# Schaltplan_Ampel.net
KiCad netlist of a schematic drawn in EAGLE
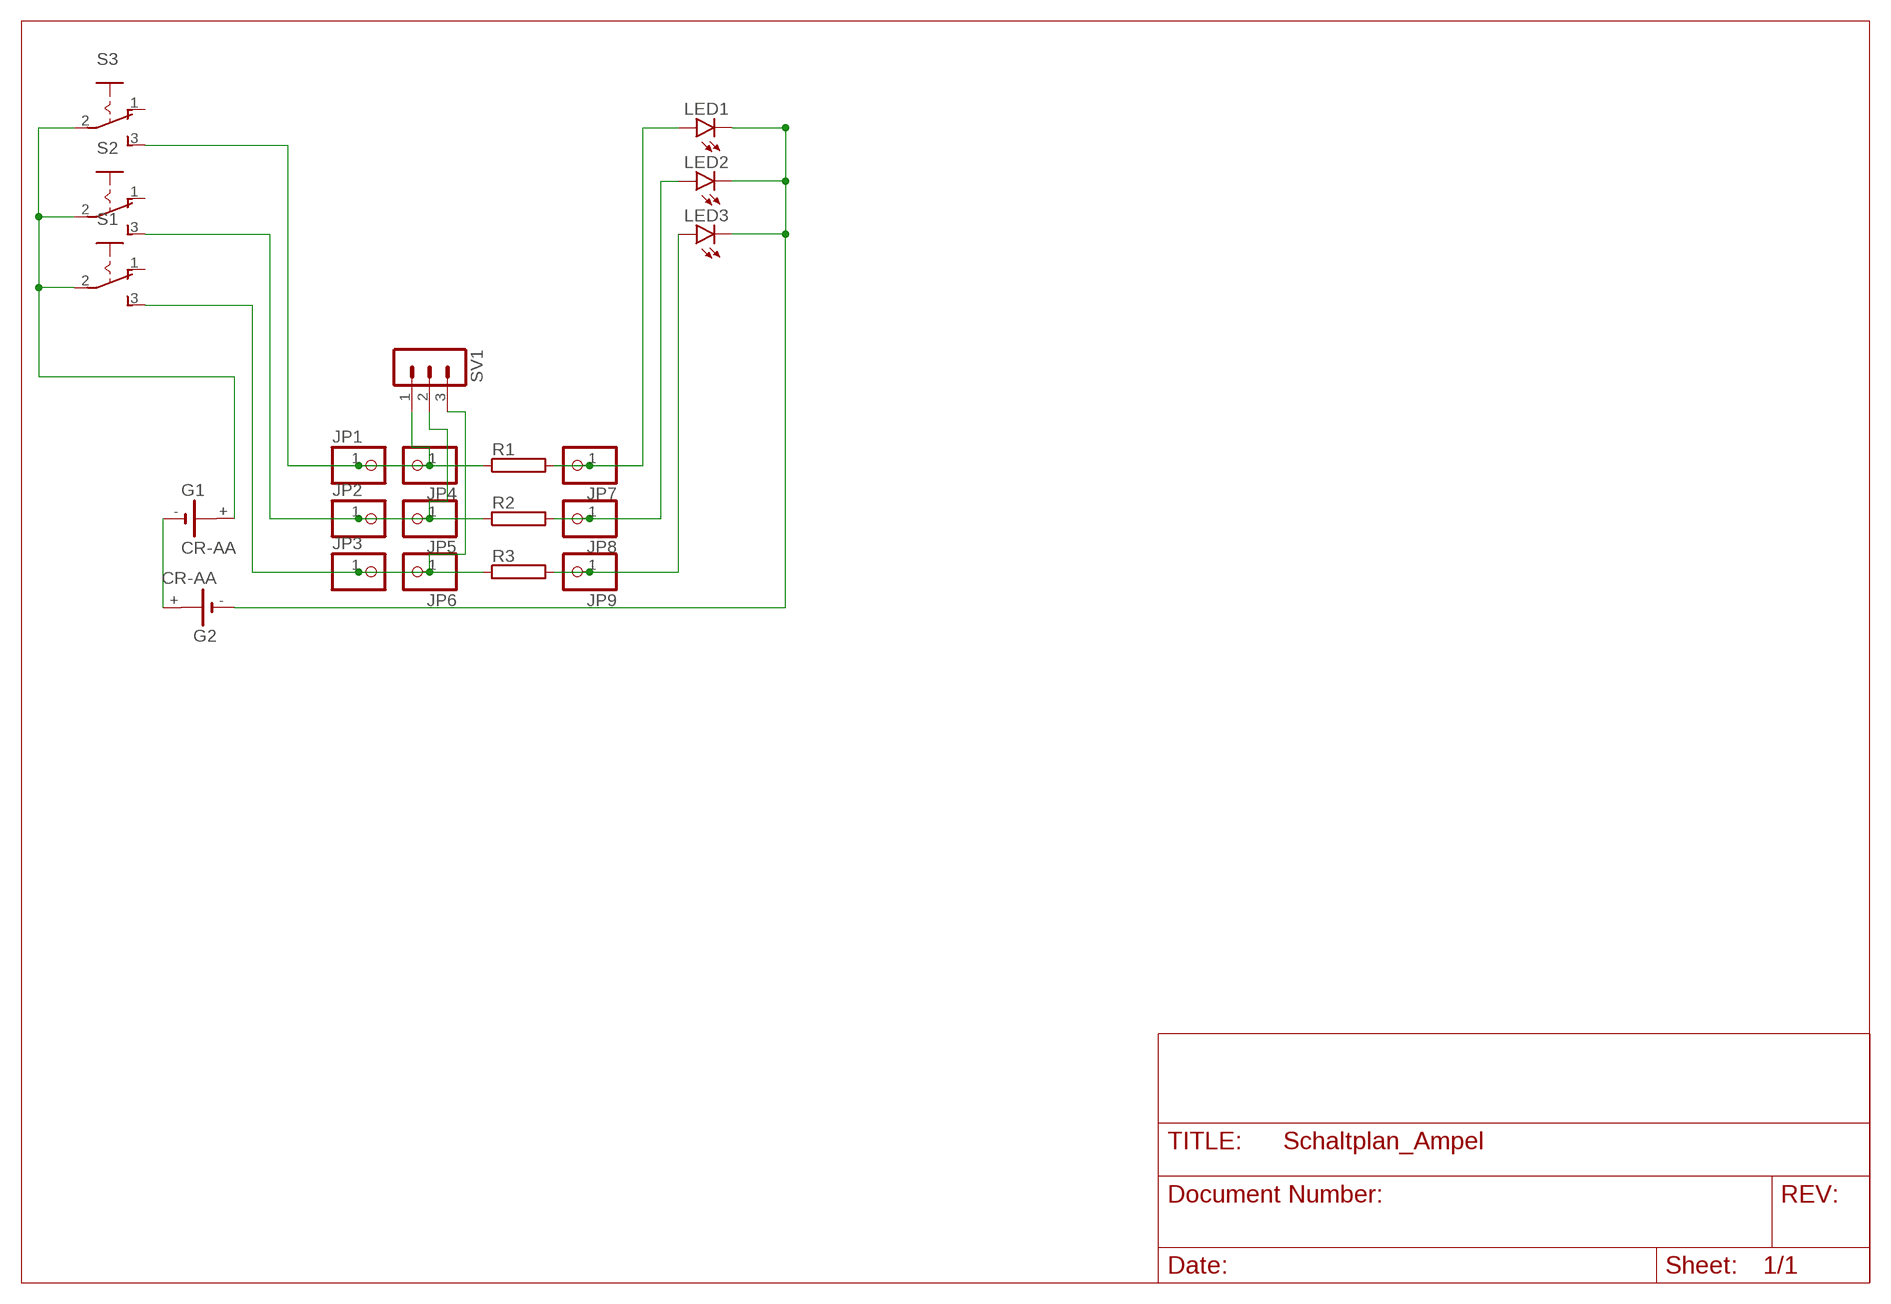
[diagram p0: schematic, sheet 1]

(export (version "E")
  (design (tool "Eeschema 10.0.6"))
  (components
    (comp (ref "G1")
      (value "CR-AA")
      (footprint "eagle-import:CRAA")
      (libsource (lib "eagle-import") (part "CR-AA"))
    )
    (comp (ref "G2")
      (value "CR-AA")
      (footprint "eagle-import:CRAA")
      (libsource (lib "eagle-import") (part "CR-AA"))
    )
    (comp (ref "JP1")
      (value "PINHD-1X1")
      (footprint "eagle-import:1X01")
      (libsource (lib "eagle-import") (part "PINHD-1X1"))
    )
    (comp (ref "JP2")
      (value "PINHD-1X1")
      (footprint "eagle-import:1X01")
      (libsource (lib "eagle-import") (part "PINHD-1X1"))
    )
    (comp (ref "JP3")
      (value "PINHD-1X1")
      (footprint "eagle-import:1X01")
      (libsource (lib "eagle-import") (part "PINHD-1X1"))
    )
    (comp (ref "JP4")
      (value "PINHD-1X1")
      (footprint "eagle-import:1X01")
      (libsource (lib "eagle-import") (part "PINHD-1X1"))
    )
    (comp (ref "JP5")
      (value "PINHD-1X1")
      (footprint "eagle-import:1X01")
      (libsource (lib "eagle-import") (part "PINHD-1X1"))
    )
    (comp (ref "JP6")
      (value "PINHD-1X1")
      (footprint "eagle-import:1X01")
      (libsource (lib "eagle-import") (part "PINHD-1X1"))
    )
    (comp (ref "JP7")
      (value "PINHD-1X1")
      (footprint "eagle-import:1X01")
      (libsource (lib "eagle-import") (part "PINHD-1X1"))
    )
    (comp (ref "JP8")
      (value "PINHD-1X1")
      (footprint "eagle-import:1X01")
      (libsource (lib "eagle-import") (part "PINHD-1X1"))
    )
    (comp (ref "JP9")
      (value "PINHD-1X1")
      (footprint "eagle-import:1X01")
      (libsource (lib "eagle-import") (part "PINHD-1X1"))
    )
    (comp (ref "LED1")
      (value "LED3MM")
      (footprint "eagle-import:LED3MM")
      (libsource (lib "eagle-import") (part "LED3MM"))
    )
    (comp (ref "LED2")
      (value "LED3MM")
      (footprint "eagle-import:LED3MM")
      (libsource (lib "eagle-import") (part "LED3MM"))
    )
    (comp (ref "LED3")
      (value "LED3MM")
      (footprint "eagle-import:LED3MM")
      (libsource (lib "eagle-import") (part "LED3MM"))
    )
    (comp (ref "R1")
      (value "RCA0002")
      (footprint "eagle-import:CA0002")
      (libsource (lib "eagle-import") (part "RCA0002"))
    )
    (comp (ref "R2")
      (value "RCA0002")
      (footprint "eagle-import:CA0002")
      (libsource (lib "eagle-import") (part "RCA0002"))
    )
    (comp (ref "R3")
      (value "RCA0002")
      (footprint "eagle-import:CA0002")
      (libsource (lib "eagle-import") (part "RCA0002"))
    )
    (comp (ref "S1")
      (value "255SB")
      (footprint "eagle-import:255SB")
      (libsource (lib "eagle-import") (part "255SB"))
    )
    (comp (ref "S2")
      (value "255SB")
      (footprint "eagle-import:255SB")
      (libsource (lib "eagle-import") (part "255SB"))
    )
    (comp (ref "S3")
      (value "255SB")
      (footprint "eagle-import:255SB")
      (libsource (lib "eagle-import") (part "255SB"))
    )
    (comp (ref "SV1")
      (value "MA03-1")
      (footprint "eagle-import:MA03-1")
      (libsource (lib "eagle-import") (part "MA03-1"))
    )
  )
  (nets
    (net (code "1") (name "Net-(G1-Pad-)") (class "Default")
      (node (ref "G1") (pin "-") (pinfunction "-_-") (pintype "passive"))
      (node (ref "G2") (pin "+") (pinfunction "+_+") (pintype "passive"))
    )
    (net (code "2") (name "Net-(JP7-Pad1)") (class "Default")
      (node (ref "JP7") (pin "1") (pinfunction "1_1") (pintype "passive"))
      (node (ref "LED1") (pin "A") (pinfunction "A_A") (pintype "passive"))
      (node (ref "R1") (pin "2") (pinfunction "2_2") (pintype "passive"))
    )
    (net (code "3") (name "Net-(JP8-Pad1)") (class "Default")
      (node (ref "JP8") (pin "1") (pinfunction "1_1") (pintype "passive"))
      (node (ref "LED2") (pin "A") (pinfunction "A_A") (pintype "passive"))
      (node (ref "R2") (pin "2") (pinfunction "2_2") (pintype "passive"))
    )
    (net (code "4") (name "Net-(JP9-Pad1)") (class "Default")
      (node (ref "JP9") (pin "1") (pinfunction "1_1") (pintype "passive"))
      (node (ref "LED3") (pin "A") (pinfunction "A_A") (pintype "passive"))
      (node (ref "R3") (pin "2") (pinfunction "2_2") (pintype "passive"))
    )
    (net (code "5") (name "Net-(LED1-C)") (class "Default")
      (node (ref "G2") (pin "-") (pinfunction "-_-") (pintype "passive"))
      (node (ref "LED1") (pin "K") (pinfunction "C_K") (pintype "passive"))
      (node (ref "LED2") (pin "K") (pinfunction "C_K") (pintype "passive"))
      (node (ref "LED3") (pin "K") (pinfunction "C_K") (pintype "passive"))
    )
    (net (code "6") (name "Net-(S1-P)") (class "Default")
      (node (ref "G1") (pin "+") (pinfunction "+_+") (pintype "passive"))
      (node (ref "S1") (pin "2") (pinfunction "P_2") (pintype "passive"))
      (node (ref "S2") (pin "2") (pinfunction "P_2") (pintype "passive"))
      (node (ref "S3") (pin "2") (pinfunction "P_2") (pintype "passive"))
    )
    (net (code "7") (name "Net-(S1-S)") (class "Default")
      (node (ref "JP3") (pin "1") (pinfunction "1_1") (pintype "passive"))
      (node (ref "JP6") (pin "1") (pinfunction "1_1") (pintype "passive"))
      (node (ref "R3") (pin "1") (pinfunction "1_1") (pintype "passive"))
      (node (ref "S1") (pin "3") (pinfunction "S_3") (pintype "passive"))
      (node (ref "SV1") (pin "3") (pinfunction "3_3") (pintype "passive"))
    )
    (net (code "8") (name "Net-(S2-S)") (class "Default")
      (node (ref "JP2") (pin "1") (pinfunction "1_1") (pintype "passive"))
      (node (ref "JP5") (pin "1") (pinfunction "1_1") (pintype "passive"))
      (node (ref "R2") (pin "1") (pinfunction "1_1") (pintype "passive"))
      (node (ref "S2") (pin "3") (pinfunction "S_3") (pintype "passive"))
      (node (ref "SV1") (pin "2") (pinfunction "2_2") (pintype "passive"))
    )
    (net (code "9") (name "Net-(S3-S)") (class "Default")
      (node (ref "JP1") (pin "1") (pinfunction "1_1") (pintype "passive"))
      (node (ref "JP4") (pin "1") (pinfunction "1_1") (pintype "passive"))
      (node (ref "R1") (pin "1") (pinfunction "1_1") (pintype "passive"))
      (node (ref "S3") (pin "3") (pinfunction "S_3") (pintype "passive"))
      (node (ref "SV1") (pin "1") (pinfunction "1_1") (pintype "passive"))
    )
    (net (code "10") (name "unconnected-(G1-+-Pad+@1)") (class "Default")
      (node (ref "G1") (pin "+@1") (pinfunction "+_+@1") (pintype "passive"))
    )
    (net (code "11") (name "unconnected-(G2-+-Pad+@1)") (class "Default")
      (node (ref "G2") (pin "+@1") (pinfunction "+_+@1") (pintype "passive"))
    )
    (net (code "12") (name "unconnected-(S1-O-Pad1)") (class "Default")
      (node (ref "S1") (pin "1") (pinfunction "O_1") (pintype "passive"))
    )
    (net (code "13") (name "unconnected-(S2-O-Pad1)") (class "Default")
      (node (ref "S2") (pin "1") (pinfunction "O_1") (pintype "passive"))
    )
    (net (code "14") (name "unconnected-(S3-O-Pad1)") (class "Default")
      (node (ref "S3") (pin "1") (pinfunction "O_1") (pintype "passive"))
    )
  )
)
